# PCB-BI8-SE-C201x.net
KiCad netlist of a schematic drawn in EAGLE
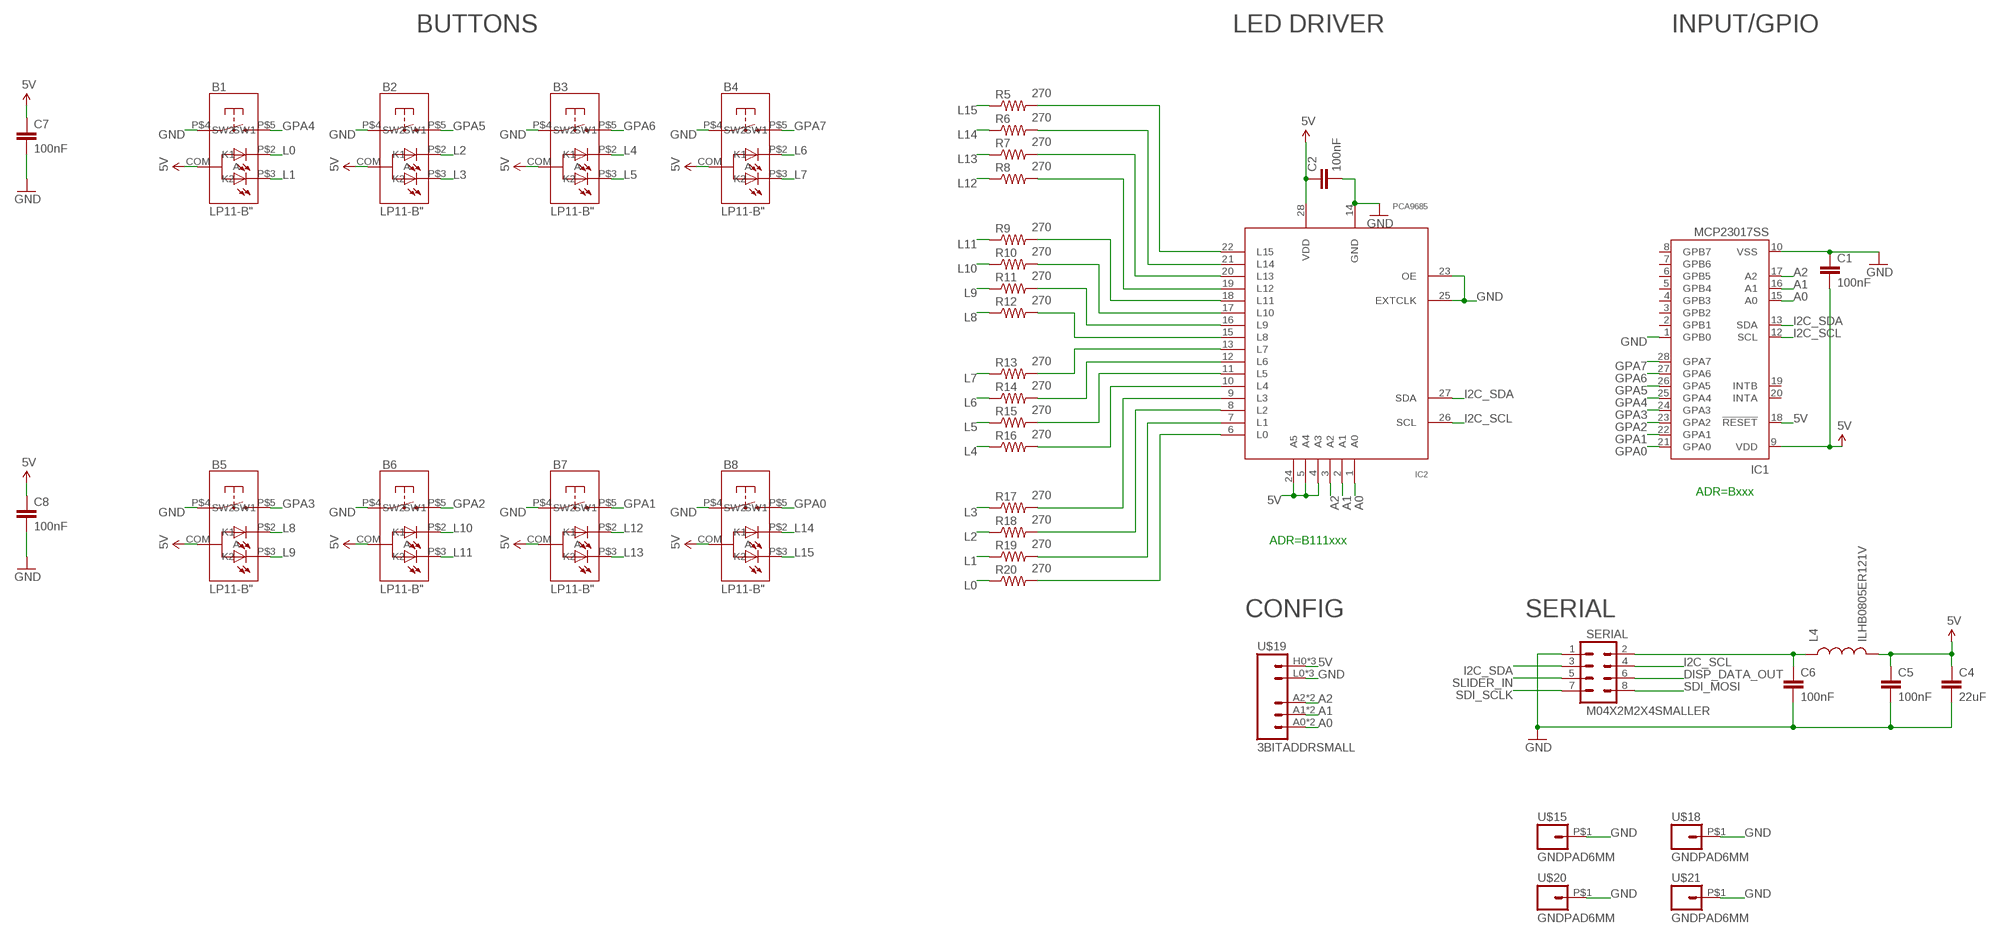
[diagram p0: schematic, sheet 1]

(export (version "E")
  (design (tool "Eeschema 10.0.6"))
  (components
    (comp (ref "B1")
      (value "LP11-B\"")
      (footprint "eagle-import:LP11")
      (libsource (lib "eagle-import") (part "LP11-B{dblquote}"))
    )
    (comp (ref "B2")
      (value "LP11-B\"")
      (footprint "eagle-import:LP11")
      (libsource (lib "eagle-import") (part "LP11-B{dblquote}"))
    )
    (comp (ref "B3")
      (value "LP11-B\"")
      (footprint "eagle-import:LP11")
      (libsource (lib "eagle-import") (part "LP11-B{dblquote}"))
    )
    (comp (ref "B4")
      (value "LP11-B\"")
      (footprint "eagle-import:LP11")
      (libsource (lib "eagle-import") (part "LP11-B{dblquote}"))
    )
    (comp (ref "B5")
      (value "LP11-B\"")
      (footprint "eagle-import:LP11")
      (libsource (lib "eagle-import") (part "LP11-B{dblquote}"))
    )
    (comp (ref "B6")
      (value "LP11-B\"")
      (footprint "eagle-import:LP11")
      (libsource (lib "eagle-import") (part "LP11-B{dblquote}"))
    )
    (comp (ref "B7")
      (value "LP11-B\"")
      (footprint "eagle-import:LP11")
      (libsource (lib "eagle-import") (part "LP11-B{dblquote}"))
    )
    (comp (ref "B8")
      (value "LP11-B\"")
      (footprint "eagle-import:LP11")
      (libsource (lib "eagle-import") (part "LP11-B{dblquote}"))
    )
    (comp (ref "C1")
      (value "100nF")
      (footprint "eagle-import:0603-CAP")
      (libsource (lib "eagle-import") (part "CAP0603-CAP"))
    )
    (comp (ref "C2")
      (value "100nF")
      (footprint "eagle-import:0603-CAP")
      (libsource (lib "eagle-import") (part "CAP0603-CAP"))
    )
    (comp (ref "C4")
      (value "22uF")
      (footprint "eagle-import:0805")
      (libsource (lib "eagle-import") (part "CAP0805"))
    )
    (comp (ref "C5")
      (value "100nF")
      (footprint "eagle-import:0603-CAP")
      (libsource (lib "eagle-import") (part "CAP0603-CAP"))
    )
    (comp (ref "C6")
      (value "100nF")
      (footprint "eagle-import:0603-CAP")
      (libsource (lib "eagle-import") (part "CAP0603-CAP"))
    )
    (comp (ref "C7")
      (value "100nF")
      (footprint "eagle-import:0603-CAP")
      (libsource (lib "eagle-import") (part "CAP0603-CAP"))
    )
    (comp (ref "C8")
      (value "100nF")
      (footprint "eagle-import:0603-CAP")
      (libsource (lib "eagle-import") (part "CAP0603-CAP"))
    )
    (comp (ref "IC1")
      (value "MCP23017SS")
      (footprint "eagle-import:SSOP28")
      (fields
        (field (name "MF") "MICROCHIP")
        (field (name "MPN") "MCP23017-E/SS")
        (field (name "MPN_1") "MCP23017-E/SS")
        (field (name "OC_FARNELL") "1467674")
        (field (name "OC_NEWARK") "31K2960")
      )
      (libsource (lib "eagle-import") (part "MCP23017SS"))
    )
    (comp (ref "IC2")
      (value "PCA9685")
      (footprint "eagle-import:TSSOP28")
      (libsource (lib "eagle-import") (part "PCA9685"))
    )
    (comp (ref "L4")
      (value "ILHB0805ER121V")
      (footprint "eagle-import:0805")
      (libsource (lib "eagle-import") (part "INDUCTOR0805"))
    )
    (comp (ref "R5")
      (value "270")
      (footprint "eagle-import:0603-RES")
      (libsource (lib "eagle-import") (part "RESISTOR0603-RES"))
    )
    (comp (ref "R6")
      (value "270")
      (footprint "eagle-import:0603-RES")
      (libsource (lib "eagle-import") (part "RESISTOR0603-RES"))
    )
    (comp (ref "R7")
      (value "270")
      (footprint "eagle-import:0603-RES")
      (libsource (lib "eagle-import") (part "RESISTOR0603-RES"))
    )
    (comp (ref "R8")
      (value "270")
      (footprint "eagle-import:0603-RES")
      (libsource (lib "eagle-import") (part "RESISTOR0603-RES"))
    )
    (comp (ref "R9")
      (value "270")
      (footprint "eagle-import:0603-RES")
      (libsource (lib "eagle-import") (part "RESISTOR0603-RES"))
    )
    (comp (ref "R10")
      (value "270")
      (footprint "eagle-import:0603-RES")
      (libsource (lib "eagle-import") (part "RESISTOR0603-RES"))
    )
    (comp (ref "R11")
      (value "270")
      (footprint "eagle-import:0603-RES")
      (libsource (lib "eagle-import") (part "RESISTOR0603-RES"))
    )
    (comp (ref "R12")
      (value "270")
      (footprint "eagle-import:0603-RES")
      (libsource (lib "eagle-import") (part "RESISTOR0603-RES"))
    )
    (comp (ref "R13")
      (value "270")
      (footprint "eagle-import:0603-RES")
      (libsource (lib "eagle-import") (part "RESISTOR0603-RES"))
    )
    (comp (ref "R14")
      (value "270")
      (footprint "eagle-import:0603-RES")
      (libsource (lib "eagle-import") (part "RESISTOR0603-RES"))
    )
    (comp (ref "R15")
      (value "270")
      (footprint "eagle-import:0603-RES")
      (libsource (lib "eagle-import") (part "RESISTOR0603-RES"))
    )
    (comp (ref "R16")
      (value "270")
      (footprint "eagle-import:0603-RES")
      (libsource (lib "eagle-import") (part "RESISTOR0603-RES"))
    )
    (comp (ref "R17")
      (value "270")
      (footprint "eagle-import:0603-RES")
      (libsource (lib "eagle-import") (part "RESISTOR0603-RES"))
    )
    (comp (ref "R18")
      (value "270")
      (footprint "eagle-import:0603-RES")
      (libsource (lib "eagle-import") (part "RESISTOR0603-RES"))
    )
    (comp (ref "R19")
      (value "270")
      (footprint "eagle-import:0603-RES")
      (libsource (lib "eagle-import") (part "RESISTOR0603-RES"))
    )
    (comp (ref "R20")
      (value "270")
      (footprint "eagle-import:0603-RES")
      (libsource (lib "eagle-import") (part "RESISTOR0603-RES"))
    )
    (comp (ref "SERIAL")
      (value "M04X2M2X4SMALLER")
      (footprint "eagle-import:M2X4SMALLER")
      (libsource (lib "eagle-import") (part "M04X2M2X4SMALLER"))
    )
    (comp (ref "U$15")
      (value "GNDPAD6MM")
      (footprint "eagle-import:3.2MMPAD6MM")
      (libsource (lib "eagle-import") (part "GNDPAD6MM"))
    )
    (comp (ref "U$18")
      (value "GNDPAD6MM")
      (footprint "eagle-import:3.2MMPAD6MM")
      (libsource (lib "eagle-import") (part "GNDPAD6MM"))
    )
    (comp (ref "U$19")
      (value "3BITADDRSMALL")
      (footprint "eagle-import:3BITADDR_SMALL")
      (libsource (lib "eagle-import") (part "3BITADDRSMALL"))
    )
    (comp (ref "U$20")
      (value "GNDPAD6MM")
      (footprint "eagle-import:3.2MMPAD6MM")
      (libsource (lib "eagle-import") (part "GNDPAD6MM"))
    )
    (comp (ref "U$21")
      (value "GNDPAD6MM")
      (footprint "eagle-import:3.2MMPAD6MM")
      (libsource (lib "eagle-import") (part "GNDPAD6MM"))
    )
  )
  (nets
    (net (code "1") (name "/A0") (class "Default")
      (node (ref "IC1") (pin "15") (pinfunction "A0_15") (pintype "input"))
      (node (ref "IC2") (pin "1") (pinfunction "A0_1") (pintype "input"))
      (node (ref "U$19") (pin "A0") (pinfunction "A0_A0") (pintype "passive"))
      (node (ref "U$19") (pin "AS0") (pinfunction "A0_AS0") (pintype "passive"))
    )
    (net (code "2") (name "/A1") (class "Default")
      (node (ref "IC1") (pin "16") (pinfunction "A1_16") (pintype "input"))
      (node (ref "IC2") (pin "2") (pinfunction "A1_2") (pintype "input"))
      (node (ref "U$19") (pin "A1") (pinfunction "A1_A1") (pintype "passive"))
      (node (ref "U$19") (pin "AS1") (pinfunction "A1_AS1") (pintype "passive"))
    )
    (net (code "3") (name "/A2") (class "Default")
      (node (ref "IC1") (pin "17") (pinfunction "A2_17") (pintype "input"))
      (node (ref "IC2") (pin "3") (pinfunction "A2_3") (pintype "input"))
      (node (ref "U$19") (pin "A2") (pinfunction "A2_A2") (pintype "passive"))
      (node (ref "U$19") (pin "AS2") (pinfunction "A2_AS2") (pintype "passive"))
    )
    (net (code "4") (name "/DISP_DATA_OUT") (class "Default")
      (node (ref "SERIAL") (pin "6") (pinfunction "6_6") (pintype "passive"))
    )
    (net (code "5") (name "/GPA0") (class "Default")
      (node (ref "B8") (pin "P$5") (pinfunction "SW2_P$5") (pintype "bidirectional"))
      (node (ref "IC1") (pin "21") (pinfunction "GPA0_21") (pintype "bidirectional"))
    )
    (net (code "6") (name "/GPA1") (class "Default")
      (node (ref "B7") (pin "P$5") (pinfunction "SW2_P$5") (pintype "bidirectional"))
      (node (ref "IC1") (pin "22") (pinfunction "GPA1_22") (pintype "bidirectional"))
    )
    (net (code "7") (name "/GPA2") (class "Default")
      (node (ref "B6") (pin "P$5") (pinfunction "SW2_P$5") (pintype "bidirectional"))
      (node (ref "IC1") (pin "23") (pinfunction "GPA2_23") (pintype "bidirectional"))
    )
    (net (code "8") (name "/GPA3") (class "Default")
      (node (ref "B5") (pin "P$5") (pinfunction "SW2_P$5") (pintype "bidirectional"))
      (node (ref "IC1") (pin "24") (pinfunction "GPA3_24") (pintype "bidirectional"))
    )
    (net (code "9") (name "/GPA4") (class "Default")
      (node (ref "B1") (pin "P$5") (pinfunction "SW2_P$5") (pintype "bidirectional"))
      (node (ref "IC1") (pin "25") (pinfunction "GPA4_25") (pintype "bidirectional"))
    )
    (net (code "10") (name "/GPA5") (class "Default")
      (node (ref "B2") (pin "P$5") (pinfunction "SW2_P$5") (pintype "bidirectional"))
      (node (ref "IC1") (pin "26") (pinfunction "GPA5_26") (pintype "bidirectional"))
    )
    (net (code "11") (name "/GPA6") (class "Default")
      (node (ref "B3") (pin "P$5") (pinfunction "SW2_P$5") (pintype "bidirectional"))
      (node (ref "IC1") (pin "27") (pinfunction "GPA6_27") (pintype "bidirectional"))
    )
    (net (code "12") (name "/GPA7") (class "Default")
      (node (ref "B4") (pin "P$5") (pinfunction "SW2_P$5") (pintype "bidirectional"))
      (node (ref "IC1") (pin "28") (pinfunction "GPA7_28") (pintype "bidirectional"))
    )
    (net (code "13") (name "/I2C_SCL") (class "Default")
      (node (ref "IC1") (pin "12") (pinfunction "SCL_12") (pintype "input"))
      (node (ref "IC2") (pin "26") (pinfunction "SCL_26") (pintype "input"))
      (node (ref "SERIAL") (pin "4") (pinfunction "4_4") (pintype "passive"))
    )
    (net (code "14") (name "/I2C_SDA") (class "Default")
      (node (ref "IC1") (pin "13") (pinfunction "SDA_13") (pintype "bidirectional"))
      (node (ref "IC2") (pin "27") (pinfunction "SDA_27") (pintype "input"))
      (node (ref "SERIAL") (pin "3") (pinfunction "3_3") (pintype "passive"))
    )
    (net (code "15") (name "/L0") (class "Default")
      (node (ref "B1") (pin "P$2") (pinfunction "K1_P$2") (pintype "bidirectional"))
      (node (ref "R20") (pin "1") (pinfunction "1_1") (pintype "passive"))
    )
    (net (code "16") (name "/L1") (class "Default")
      (node (ref "B1") (pin "P$3") (pinfunction "K2_P$3") (pintype "bidirectional"))
      (node (ref "R19") (pin "1") (pinfunction "1_1") (pintype "passive"))
    )
    (net (code "17") (name "/L2") (class "Default")
      (node (ref "B2") (pin "P$2") (pinfunction "K1_P$2") (pintype "bidirectional"))
      (node (ref "R18") (pin "1") (pinfunction "1_1") (pintype "passive"))
    )
    (net (code "18") (name "/L3") (class "Default")
      (node (ref "B2") (pin "P$3") (pinfunction "K2_P$3") (pintype "bidirectional"))
      (node (ref "R17") (pin "1") (pinfunction "1_1") (pintype "passive"))
    )
    (net (code "19") (name "/L4") (class "Default")
      (node (ref "B3") (pin "P$2") (pinfunction "K1_P$2") (pintype "bidirectional"))
      (node (ref "R16") (pin "1") (pinfunction "1_1") (pintype "passive"))
    )
    (net (code "20") (name "/L5") (class "Default")
      (node (ref "B3") (pin "P$3") (pinfunction "K2_P$3") (pintype "bidirectional"))
      (node (ref "R15") (pin "1") (pinfunction "1_1") (pintype "passive"))
    )
    (net (code "21") (name "/L6") (class "Default")
      (node (ref "B4") (pin "P$2") (pinfunction "K1_P$2") (pintype "bidirectional"))
      (node (ref "R14") (pin "1") (pinfunction "1_1") (pintype "passive"))
    )
    (net (code "22") (name "/L7") (class "Default")
      (node (ref "B4") (pin "P$3") (pinfunction "K2_P$3") (pintype "bidirectional"))
      (node (ref "R13") (pin "1") (pinfunction "1_1") (pintype "passive"))
    )
    (net (code "23") (name "/L8") (class "Default")
      (node (ref "B5") (pin "P$2") (pinfunction "K1_P$2") (pintype "bidirectional"))
      (node (ref "R12") (pin "1") (pinfunction "1_1") (pintype "passive"))
    )
    (net (code "24") (name "/L9") (class "Default")
      (node (ref "B5") (pin "P$3") (pinfunction "K2_P$3") (pintype "bidirectional"))
      (node (ref "R11") (pin "1") (pinfunction "1_1") (pintype "passive"))
    )
    (net (code "25") (name "/L10") (class "Default")
      (node (ref "B6") (pin "P$2") (pinfunction "K1_P$2") (pintype "bidirectional"))
      (node (ref "R10") (pin "1") (pinfunction "1_1") (pintype "passive"))
    )
    (net (code "26") (name "/L11") (class "Default")
      (node (ref "B6") (pin "P$3") (pinfunction "K2_P$3") (pintype "bidirectional"))
      (node (ref "R9") (pin "1") (pinfunction "1_1") (pintype "passive"))
    )
    (net (code "27") (name "/L12") (class "Default")
      (node (ref "B7") (pin "P$2") (pinfunction "K1_P$2") (pintype "bidirectional"))
      (node (ref "R8") (pin "1") (pinfunction "1_1") (pintype "passive"))
    )
    (net (code "28") (name "/L13") (class "Default")
      (node (ref "B7") (pin "P$3") (pinfunction "K2_P$3") (pintype "bidirectional"))
      (node (ref "R7") (pin "1") (pinfunction "1_1") (pintype "passive"))
    )
    (net (code "29") (name "/L14") (class "Default")
      (node (ref "B8") (pin "P$2") (pinfunction "K1_P$2") (pintype "bidirectional"))
      (node (ref "R6") (pin "1") (pinfunction "1_1") (pintype "passive"))
    )
    (net (code "30") (name "/L15") (class "Default")
      (node (ref "B8") (pin "P$3") (pinfunction "K2_P$3") (pintype "bidirectional"))
      (node (ref "R5") (pin "1") (pinfunction "1_1") (pintype "passive"))
    )
    (net (code "31") (name "/SDI_MOSI") (class "Default")
      (node (ref "SERIAL") (pin "8") (pinfunction "8_8") (pintype "passive"))
    )
    (net (code "32") (name "/SDI_SCLK") (class "Default")
      (node (ref "SERIAL") (pin "7") (pinfunction "7_7") (pintype "passive"))
    )
    (net (code "33") (name "/SLIDER_IN") (class "Default")
      (node (ref "SERIAL") (pin "5") (pinfunction "5_5") (pintype "passive"))
    )
    (net (code "34") (name "5V") (class "Default")
      (node (ref "B1") (pin "COM") (pinfunction "A_COM") (pintype "bidirectional"))
      (node (ref "B2") (pin "COM") (pinfunction "A_COM") (pintype "bidirectional"))
      (node (ref "B3") (pin "COM") (pinfunction "A_COM") (pintype "bidirectional"))
      (node (ref "B4") (pin "COM") (pinfunction "A_COM") (pintype "bidirectional"))
      (node (ref "B5") (pin "COM") (pinfunction "A_COM") (pintype "bidirectional"))
      (node (ref "B6") (pin "COM") (pinfunction "A_COM") (pintype "bidirectional"))
      (node (ref "B7") (pin "COM") (pinfunction "A_COM") (pintype "bidirectional"))
      (node (ref "B8") (pin "COM") (pinfunction "A_COM") (pintype "bidirectional"))
      (node (ref "C1") (pin "2") (pinfunction "2_2") (pintype "passive"))
      (node (ref "C2") (pin "1") (pinfunction "1_1") (pintype "passive"))
      (node (ref "C4") (pin "1") (pinfunction "1_1") (pintype "passive"))
      (node (ref "C5") (pin "1") (pinfunction "1_1") (pintype "passive"))
      (node (ref "C7") (pin "1") (pinfunction "1_1") (pintype "passive"))
      (node (ref "C8") (pin "1") (pinfunction "1_1") (pintype "passive"))
      (node (ref "IC1") (pin "18") (pinfunction "~{RESET}_18") (pintype "input"))
      (node (ref "IC1") (pin "9") (pinfunction "VDD_9") (pintype "power_in"))
      (node (ref "IC2") (pin "24") (pinfunction "A5_24") (pintype "input"))
      (node (ref "IC2") (pin "28") (pinfunction "VDD_28") (pintype "power_in"))
      (node (ref "IC2") (pin "4") (pinfunction "A3_4") (pintype "input"))
      (node (ref "IC2") (pin "5") (pinfunction "A4_5") (pintype "input"))
      (node (ref "L4") (pin "2") (pinfunction "2_2") (pintype "passive"))
      (node (ref "U$19") (pin "H0") (pinfunction "VCC_H0") (pintype "passive"))
      (node (ref "U$19") (pin "H1") (pinfunction "VCC_H1") (pintype "passive"))
      (node (ref "U$19") (pin "H2") (pinfunction "VCC_H2") (pintype "passive"))
    )
    (net (code "35") (name "GND") (class "Default")
      (node (ref "B1") (pin "P$4") (pinfunction "SW1_P$4") (pintype "bidirectional"))
      (node (ref "B2") (pin "P$4") (pinfunction "SW1_P$4") (pintype "bidirectional"))
      (node (ref "B3") (pin "P$4") (pinfunction "SW1_P$4") (pintype "bidirectional"))
      (node (ref "B4") (pin "P$4") (pinfunction "SW1_P$4") (pintype "bidirectional"))
      (node (ref "B5") (pin "P$4") (pinfunction "SW1_P$4") (pintype "bidirectional"))
      (node (ref "B6") (pin "P$4") (pinfunction "SW1_P$4") (pintype "bidirectional"))
      (node (ref "B7") (pin "P$4") (pinfunction "SW1_P$4") (pintype "bidirectional"))
      (node (ref "B8") (pin "P$4") (pinfunction "SW1_P$4") (pintype "bidirectional"))
      (node (ref "C1") (pin "1") (pinfunction "1_1") (pintype "passive"))
      (node (ref "C2") (pin "2") (pinfunction "2_2") (pintype "passive"))
      (node (ref "C4") (pin "2") (pinfunction "2_2") (pintype "passive"))
      (node (ref "C5") (pin "2") (pinfunction "2_2") (pintype "passive"))
      (node (ref "C6") (pin "2") (pinfunction "2_2") (pintype "passive"))
      (node (ref "C7") (pin "2") (pinfunction "2_2") (pintype "passive"))
      (node (ref "C8") (pin "2") (pinfunction "2_2") (pintype "passive"))
      (node (ref "IC1") (pin "1") (pinfunction "GPB0_1") (pintype "bidirectional"))
      (node (ref "IC1") (pin "10") (pinfunction "VSS_10") (pintype "power_in"))
      (node (ref "IC2") (pin "14") (pinfunction "GND_14") (pintype "power_in"))
      (node (ref "IC2") (pin "23") (pinfunction "OE_23") (pintype "input"))
      (node (ref "IC2") (pin "25") (pinfunction "EXTCLK_25") (pintype "input"))
      (node (ref "SERIAL") (pin "1") (pinfunction "1_1") (pintype "passive"))
      (node (ref "U$15") (pin "P$1") (pinfunction "1_P$1") (pintype "passive"))
      (node (ref "U$18") (pin "P$1") (pinfunction "1_P$1") (pintype "passive"))
      (node (ref "U$19") (pin "L0") (pinfunction "GND_L0") (pintype "passive"))
      (node (ref "U$19") (pin "L1") (pinfunction "GND_L1") (pintype "passive"))
      (node (ref "U$19") (pin "L2") (pinfunction "GND_L2") (pintype "passive"))
      (node (ref "U$20") (pin "P$1") (pinfunction "1_P$1") (pintype "passive"))
      (node (ref "U$21") (pin "P$1") (pinfunction "1_P$1") (pintype "passive"))
    )
    (net (code "36") (name "Net-(C6-Pad1)") (class "Default")
      (node (ref "C6") (pin "1") (pinfunction "1_1") (pintype "passive"))
      (node (ref "L4") (pin "1") (pinfunction "1_1") (pintype "passive"))
      (node (ref "SERIAL") (pin "2") (pinfunction "2_2") (pintype "passive"))
    )
    (net (code "37") (name "Net-(IC2-L0)") (class "Default")
      (node (ref "IC2") (pin "6") (pinfunction "L0_6") (pintype "output"))
      (node (ref "R20") (pin "2") (pinfunction "2_2") (pintype "passive"))
    )
    (net (code "38") (name "Net-(IC2-L1)") (class "Default")
      (node (ref "IC2") (pin "7") (pinfunction "L1_7") (pintype "output"))
      (node (ref "R19") (pin "2") (pinfunction "2_2") (pintype "passive"))
    )
    (net (code "39") (name "Net-(IC2-L2)") (class "Default")
      (node (ref "IC2") (pin "8") (pinfunction "L2_8") (pintype "output"))
      (node (ref "R18") (pin "2") (pinfunction "2_2") (pintype "passive"))
    )
    (net (code "40") (name "Net-(IC2-L3)") (class "Default")
      (node (ref "IC2") (pin "9") (pinfunction "L3_9") (pintype "output"))
      (node (ref "R17") (pin "2") (pinfunction "2_2") (pintype "passive"))
    )
    (net (code "41") (name "Net-(IC2-L4)") (class "Default")
      (node (ref "IC2") (pin "10") (pinfunction "L4_10") (pintype "output"))
      (node (ref "R16") (pin "2") (pinfunction "2_2") (pintype "passive"))
    )
    (net (code "42") (name "Net-(IC2-L5)") (class "Default")
      (node (ref "IC2") (pin "11") (pinfunction "L5_11") (pintype "output"))
      (node (ref "R15") (pin "2") (pinfunction "2_2") (pintype "passive"))
    )
    (net (code "43") (name "Net-(IC2-L6)") (class "Default")
      (node (ref "IC2") (pin "12") (pinfunction "L6_12") (pintype "output"))
      (node (ref "R14") (pin "2") (pinfunction "2_2") (pintype "passive"))
    )
    (net (code "44") (name "Net-(IC2-L7)") (class "Default")
      (node (ref "IC2") (pin "13") (pinfunction "L7_13") (pintype "output"))
      (node (ref "R13") (pin "2") (pinfunction "2_2") (pintype "passive"))
    )
    (net (code "45") (name "Net-(IC2-L8)") (class "Default")
      (node (ref "IC2") (pin "15") (pinfunction "L8_15") (pintype "output"))
      (node (ref "R12") (pin "2") (pinfunction "2_2") (pintype "passive"))
    )
    (net (code "46") (name "Net-(IC2-L9)") (class "Default")
      (node (ref "IC2") (pin "16") (pinfunction "L9_16") (pintype "output"))
      (node (ref "R11") (pin "2") (pinfunction "2_2") (pintype "passive"))
    )
    (net (code "47") (name "Net-(IC2-L10)") (class "Default")
      (node (ref "IC2") (pin "17") (pinfunction "L10_17") (pintype "output"))
      (node (ref "R10") (pin "2") (pinfunction "2_2") (pintype "passive"))
    )
    (net (code "48") (name "Net-(IC2-L11)") (class "Default")
      (node (ref "IC2") (pin "18") (pinfunction "L11_18") (pintype "output"))
      (node (ref "R9") (pin "2") (pinfunction "2_2") (pintype "passive"))
    )
    (net (code "49") (name "Net-(IC2-L12)") (class "Default")
      (node (ref "IC2") (pin "19") (pinfunction "L12_19") (pintype "output"))
      (node (ref "R8") (pin "2") (pinfunction "2_2") (pintype "passive"))
    )
    (net (code "50") (name "Net-(IC2-L13)") (class "Default")
      (node (ref "IC2") (pin "20") (pinfunction "L13_20") (pintype "output"))
      (node (ref "R7") (pin "2") (pinfunction "2_2") (pintype "passive"))
    )
    (net (code "51") (name "Net-(IC2-L14)") (class "Default")
      (node (ref "IC2") (pin "21") (pinfunction "L14_21") (pintype "output"))
      (node (ref "R6") (pin "2") (pinfunction "2_2") (pintype "passive"))
    )
    (net (code "52") (name "Net-(IC2-L15)") (class "Default")
      (node (ref "IC2") (pin "22") (pinfunction "L15_22") (pintype "output"))
      (node (ref "R5") (pin "2") (pinfunction "2_2") (pintype "passive"))
    )
    (net (code "53") (name "unconnected-(IC1-GPB1-Pad2)") (class "Default")
      (node (ref "IC1") (pin "2") (pinfunction "GPB1_2") (pintype "bidirectional"))
    )
    (net (code "54") (name "unconnected-(IC1-GPB2-Pad3)") (class "Default")
      (node (ref "IC1") (pin "3") (pinfunction "GPB2_3") (pintype "bidirectional"))
    )
    (net (code "55") (name "unconnected-(IC1-GPB3-Pad4)") (class "Default")
      (node (ref "IC1") (pin "4") (pinfunction "GPB3_4") (pintype "bidirectional"))
    )
    (net (code "56") (name "unconnected-(IC1-GPB4-Pad5)") (class "Default")
      (node (ref "IC1") (pin "5") (pinfunction "GPB4_5") (pintype "bidirectional"))
    )
    (net (code "57") (name "unconnected-(IC1-GPB5-Pad6)") (class "Default")
      (node (ref "IC1") (pin "6") (pinfunction "GPB5_6") (pintype "bidirectional"))
    )
    (net (code "58") (name "unconnected-(IC1-GPB6-Pad7)") (class "Default")
      (node (ref "IC1") (pin "7") (pinfunction "GPB6_7") (pintype "bidirectional"))
    )
    (net (code "59") (name "unconnected-(IC1-GPB7-Pad8)") (class "Default")
      (node (ref "IC1") (pin "8") (pinfunction "GPB7_8") (pintype "bidirectional"))
    )
    (net (code "60") (name "unconnected-(IC1-INTA-Pad20)") (class "Default")
      (node (ref "IC1") (pin "20") (pinfunction "INTA_20") (pintype "output"))
    )
    (net (code "61") (name "unconnected-(IC1-INTB-Pad19)") (class "Default")
      (node (ref "IC1") (pin "19") (pinfunction "INTB_19") (pintype "output"))
    )
  )
)
